# LEDLayout.net
KiCad netlist of a schematic drawn in EAGLE
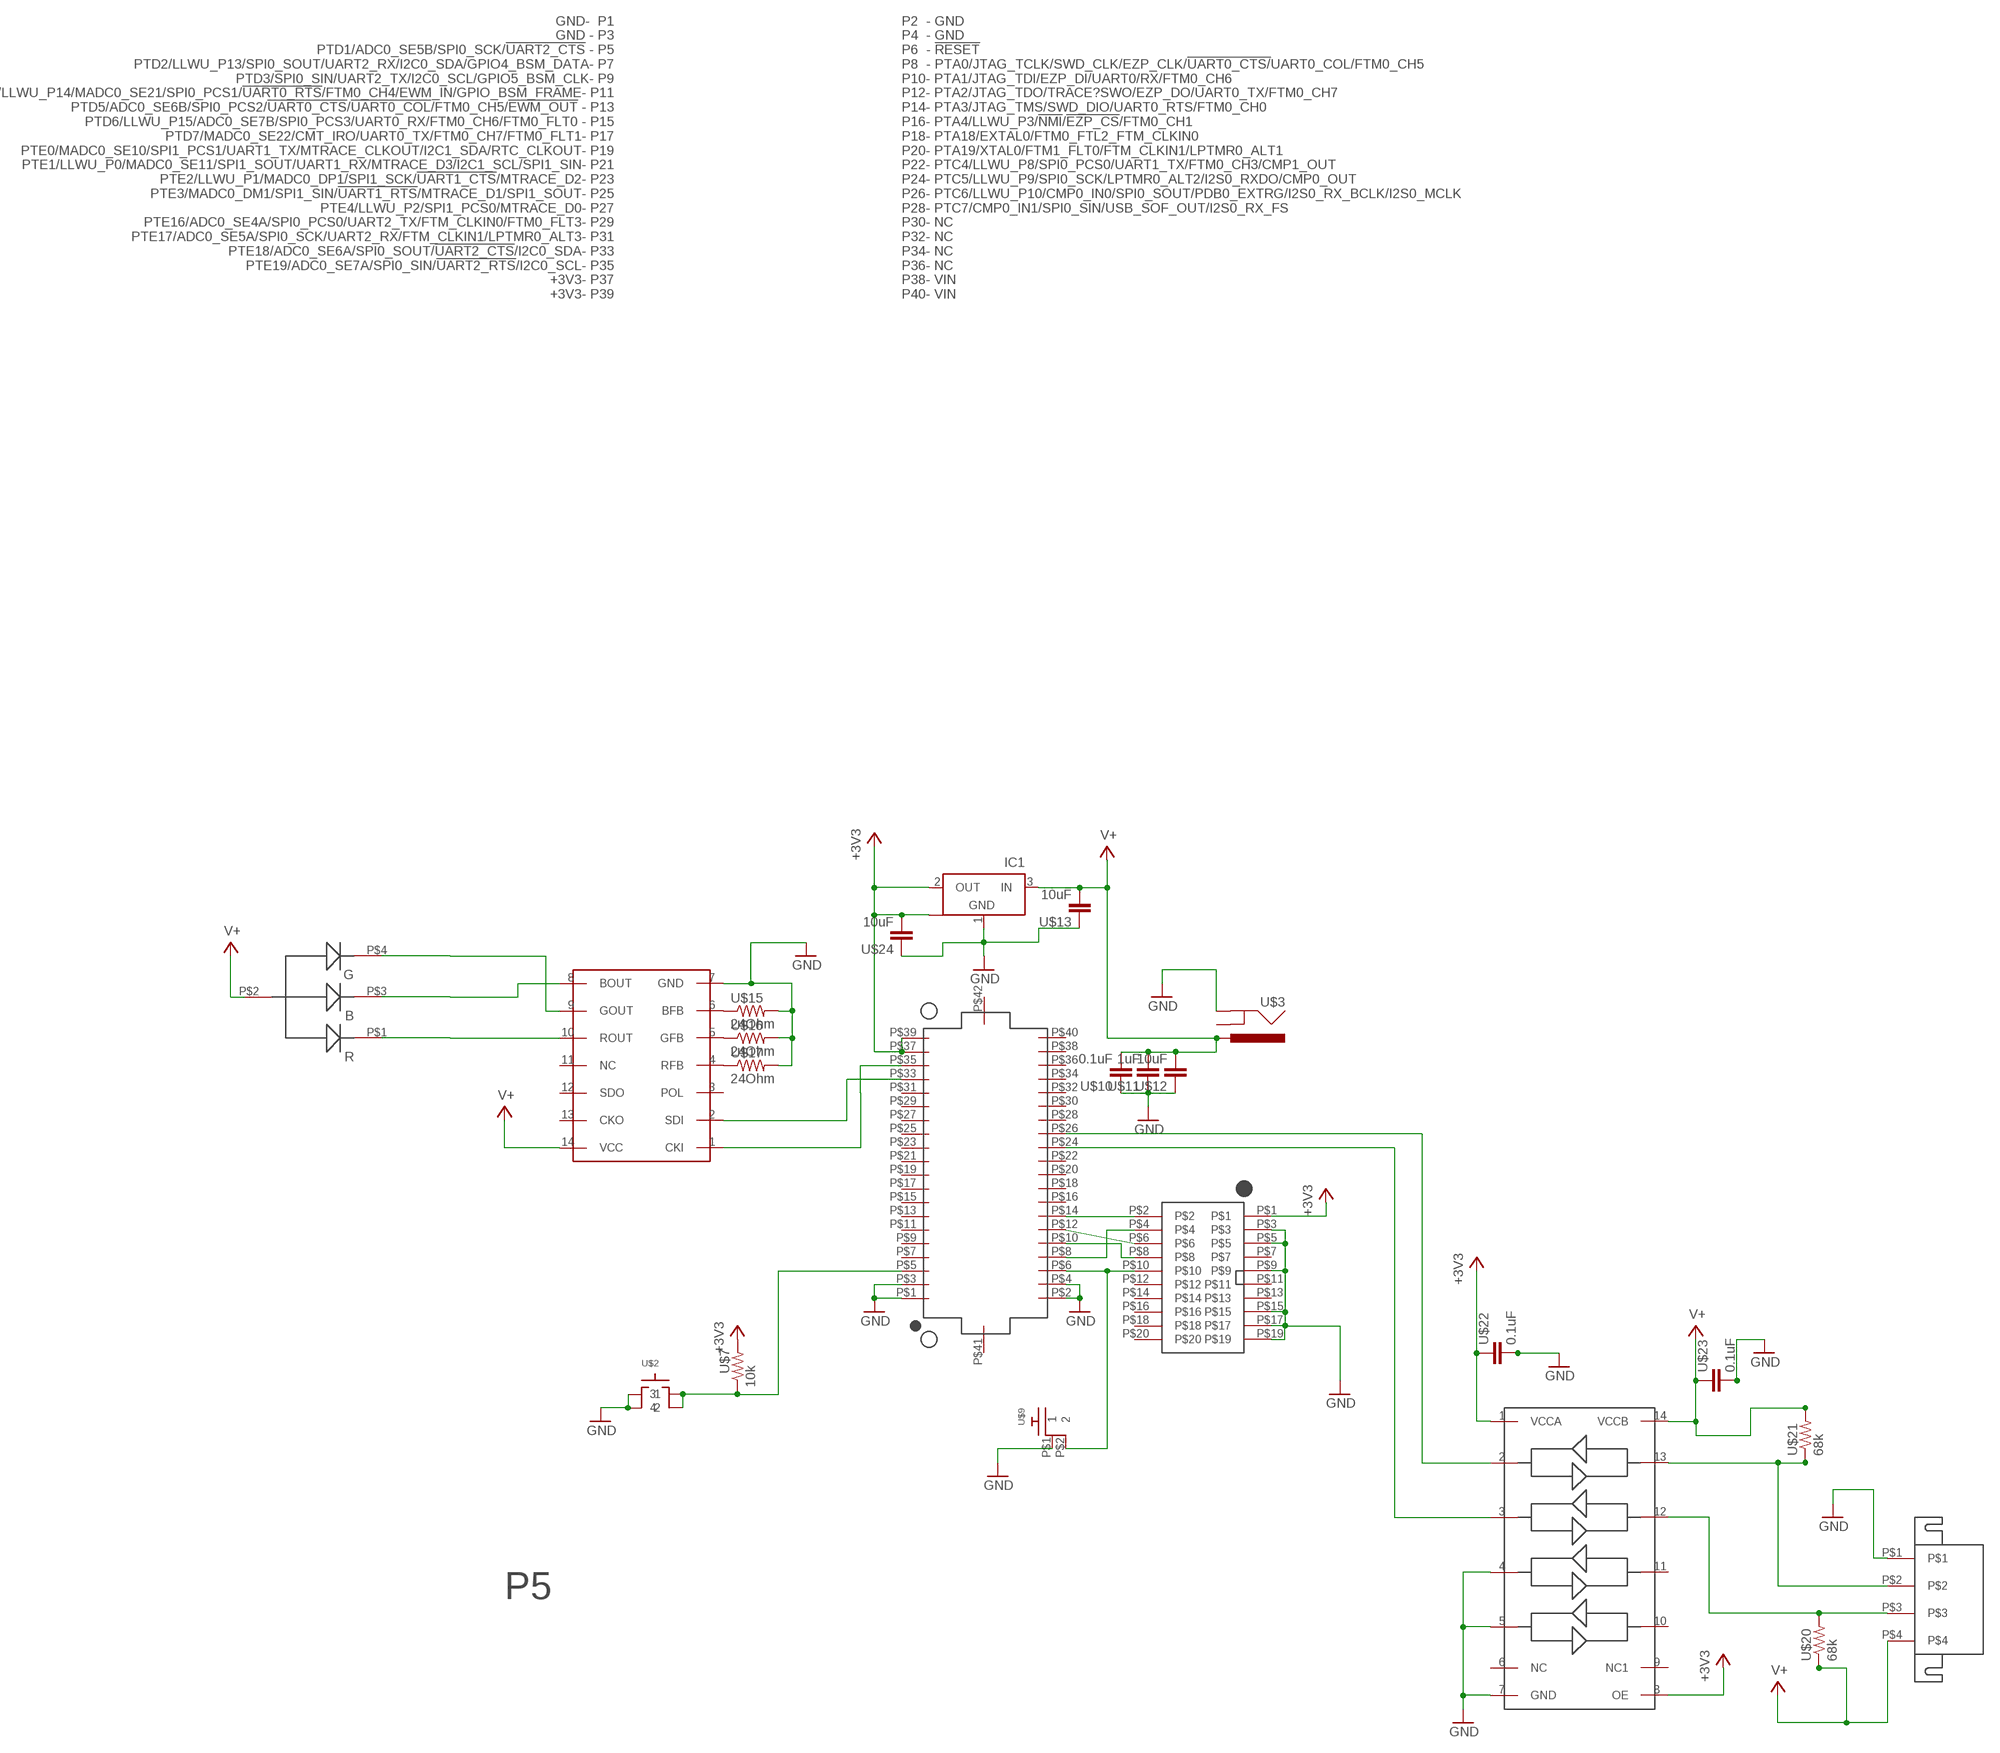
[diagram p0: schematic, sheet 1]

(export (version "E")
  (design (tool "Eeschema 10.0.6"))
  (components
    (comp (ref "IC1")
      (value "NCP1117ST33T3G_1")
      (footprint "eagle-import:SOT223")
      (fields (field (name "MFGN") "OnSemi") (field (name "MFGP") "NCP1117ST33T3G"))
      (libsource (lib "eagle-import") (part "NCP1117ST33T3G_1"))
    )
    (comp (ref "U$1")
      (value "MATE-N-LOK_643230-1")
      (footprint "eagle-import:MATE-N-LOK_643230-1")
      (fields (field (name "MFGN") "TE Connectivity") (field (name "MFGP") "643230-1"))
      (libsource (lib "eagle-import") (part "MATE-N-LOK_643230-1"))
    )
    (comp (ref "U$2")
      (value "SWITCH-TACTILE")
      (footprint "eagle-import:ESWITCH-TL3301PF")
      (libsource (lib "eagle-import") (part "SWITCH-TACTILE"))
    )
    (comp (ref "U$3")
      (value "BARREL_CUI_PJ-002A")
      (footprint "eagle-import:BARREL_CUI_PJ-002A")
      (libsource (lib "eagle-import") (part "BARREL_CUI_PJ-002A"))
    )
    (comp (ref "U$4")
      (value "DF12_F")
      (footprint "eagle-import:DF12_F")
      (fields (field (name "MFGN") "Hirose") (field (name "MFGP") "DF12(3.0)-40DP-0.5V(86)"))
      (libsource (lib "eagle-import") (part "DF12_F"))
    )
    (comp (ref "U$5")
      (value "RGLBED")
      (footprint "eagle-import:RGBLED")
      (libsource (lib "eagle-import") (part "RGLBED"))
    )
    (comp (ref "U$6")
      (value "TXB0104")
      (footprint "eagle-import:PW_R-PDSO-G14")
      (fields (field (name "MFGN") "Texas Instruments"))
      (libsource (lib "eagle-import") (part "TXB0104"))
    )
    (comp (ref "U$7")
      (value "10k")
      (footprint "eagle-import:RF-C0805")
      (libsource (lib "eagle-import") (part "RF-R0805"))
    )
    (comp (ref "U$8")
      (value "WS2801")
      (footprint "eagle-import:SO14")
      (libsource (lib "eagle-import") (part "WS2801"))
    )
    (comp (ref "U$9")
      (value "RA_BUTTON")
      (footprint "eagle-import:RA_BUTTON")
      (libsource (lib "eagle-import") (part "RA_BUTTON"))
    )
    (comp (ref "U$10")
      (value "0.1uF")
      (footprint "eagle-import:C0805")
      (libsource (lib "eagle-import") (part "RF-C0805"))
    )
    (comp (ref "U$11")
      (value "1uF")
      (footprint "eagle-import:C0805")
      (libsource (lib "eagle-import") (part "RF-C0805"))
    )
    (comp (ref "U$12")
      (value "10uF")
      (footprint "eagle-import:C0805")
      (libsource (lib "eagle-import") (part "RF-C0805"))
    )
    (comp (ref "U$13")
      (value "10uF")
      (footprint "eagle-import:C0805")
      (libsource (lib "eagle-import") (part "RF-C0805"))
    )
    (comp (ref "U$15")
      (value "24Ohm")
      (footprint "eagle-import:RF-C0805")
      (libsource (lib "eagle-import") (part "RF-R0805"))
    )
    (comp (ref "U$16")
      (value "24Ohm")
      (footprint "eagle-import:RF-C0805")
      (libsource (lib "eagle-import") (part "RF-R0805"))
    )
    (comp (ref "U$17")
      (value "24Ohm")
      (footprint "eagle-import:RF-C0805")
      (libsource (lib "eagle-import") (part "RF-R0805"))
    )
    (comp (ref "U$19")
      (value "2X10JTAG")
      (footprint "eagle-import:2X10JTAG")
      (libsource (lib "eagle-import") (part "2X10JTAG"))
    )
    (comp (ref "U$20")
      (value "68k")
      (footprint "eagle-import:RF-C0805")
      (libsource (lib "eagle-import") (part "RF-R0805"))
    )
    (comp (ref "U$21")
      (value "68k")
      (footprint "eagle-import:RF-C0805")
      (libsource (lib "eagle-import") (part "RF-R0805"))
    )
    (comp (ref "U$22")
      (value "0.1uF")
      (footprint "eagle-import:C0805")
      (libsource (lib "eagle-import") (part "RF-C0805"))
    )
    (comp (ref "U$23")
      (value "0.1uF")
      (footprint "eagle-import:C0805")
      (libsource (lib "eagle-import") (part "RF-C0805"))
    )
    (comp (ref "U$24")
      (value "10uF")
      (footprint "eagle-import:C0805")
      (libsource (lib "eagle-import") (part "RF-C0805"))
    )
  )
  (nets
    (net (code "1") (name "+3V3") (class "Default")
      (node (ref "IC1") (pin "2") (pinfunction "OUT_2") (pintype "power_in"))
      (node (ref "IC1") (pin "4") (pinfunction "OUT1_4") (pintype "power_in"))
      (node (ref "U$19") (pin "P$1") (pinfunction "P$1_P$1") (pintype "bidirectional"))
      (node (ref "U$22") (pin "1") (pinfunction "1_1") (pintype "passive"))
      (node (ref "U$24") (pin "2") (pinfunction "2_2") (pintype "passive"))
      (node (ref "U$4") (pin "P$37") (pinfunction "+3V3_P$37") (pintype "bidirectional"))
      (node (ref "U$4") (pin "P$39") (pinfunction "+3V3_P$39") (pintype "bidirectional"))
      (node (ref "U$6") (pin "1") (pinfunction "VCCA_1") (pintype "bidirectional"))
      (node (ref "U$6") (pin "8") (pinfunction "OE_8") (pintype "bidirectional"))
      (node (ref "U$7") (pin "2") (pinfunction "2_2") (pintype "passive"))
    )
    (net (code "2") (name "GND") (class "Default")
      (node (ref "IC1") (pin "1") (pinfunction "GND_1") (pintype "power_in"))
      (node (ref "U$1") (pin "P$1") (pinfunction "P$1_P$1") (pintype "bidirectional"))
      (node (ref "U$10") (pin "1") (pinfunction "1_1") (pintype "passive"))
      (node (ref "U$11") (pin "1") (pinfunction "1_1") (pintype "passive"))
      (node (ref "U$12") (pin "1") (pinfunction "1_1") (pintype "passive"))
      (node (ref "U$13") (pin "1") (pinfunction "1_1") (pintype "passive"))
      (node (ref "U$15") (pin "2") (pinfunction "2_2") (pintype "passive"))
      (node (ref "U$16") (pin "2") (pinfunction "2_2") (pintype "passive"))
      (node (ref "U$17") (pin "2") (pinfunction "2_2") (pintype "passive"))
      (node (ref "U$19") (pin "P$15") (pinfunction "P$15_P$15") (pintype "bidirectional"))
      (node (ref "U$19") (pin "P$17") (pinfunction "P$17_P$17") (pintype "bidirectional"))
      (node (ref "U$19") (pin "P$19") (pinfunction "P$19_P$19") (pintype "bidirectional"))
      (node (ref "U$19") (pin "P$3") (pinfunction "P$3_P$3") (pintype "bidirectional"))
      (node (ref "U$19") (pin "P$5") (pinfunction "P$5_P$5") (pintype "bidirectional"))
      (node (ref "U$19") (pin "P$9") (pinfunction "P$9_P$9") (pintype "bidirectional"))
      (node (ref "U$2") (pin "1") (pinfunction "1_1") (pintype "input"))
      (node (ref "U$2") (pin "2") (pinfunction "2_2") (pintype "input"))
      (node (ref "U$22") (pin "2") (pinfunction "2_2") (pintype "passive"))
      (node (ref "U$23") (pin "2") (pinfunction "2_2") (pintype "passive"))
      (node (ref "U$24") (pin "1") (pinfunction "1_1") (pintype "passive"))
      (node (ref "U$3") (pin "P$2") (pinfunction "GND_P$2") (pintype "bidirectional"))
      (node (ref "U$4") (pin "P$1") (pinfunction "GND_P$1") (pintype "bidirectional"))
      (node (ref "U$4") (pin "P$2") (pinfunction "GND_P$2") (pintype "bidirectional"))
      (node (ref "U$4") (pin "P$3") (pinfunction "GND_P$3") (pintype "bidirectional"))
      (node (ref "U$4") (pin "P$4") (pinfunction "GND_P$4") (pintype "bidirectional"))
      (node (ref "U$6") (pin "4") (pinfunction "P$4_4") (pintype "bidirectional"))
      (node (ref "U$6") (pin "5") (pinfunction "P$5_5") (pintype "bidirectional"))
      (node (ref "U$6") (pin "7") (pinfunction "GND_7") (pintype "bidirectional"))
      (node (ref "U$8") (pin "7") (pinfunction "GND_7") (pintype "bidirectional"))
      (node (ref "U$9") (pin "P$1") (pinfunction "1_P$1") (pintype "input"))
    )
    (net (code "3") (name "Net-(U$4-PTA0{slash}JTAG_TCLK{slash}SWD_CLK{slash}EZP_CLK{slash}~{UART0_CTS{slash}}UART0_COL{slash}FTM0_CH5)") (class "Default")
      (node (ref "U$19") (pin "P$4") (pinfunction "P$4_P$4") (pintype "bidirectional"))
      (node (ref "U$4") (pin "P$8") (pinfunction "PTA0/JTAG_TCLK/SWD_CLK/EZP_CLK/~{UART0_CTS/}UART0_COL/FTM0_CH5_P$8") (pintype "bidirectional"))
    )
    (net (code "4") (name "Net-(U$4-PTA1{slash}JTAG_TDI{slash}EZP_DI{slash}UART0{slash}RX{slash}FTM0_CH6)") (class "Default")
      (node (ref "U$19") (pin "P$8") (pinfunction "P$8_P$8") (pintype "bidirectional"))
      (node (ref "U$4") (pin "P$10") (pinfunction "PTA1/JTAG_TDI/EZP_DI/UART0/RX/FTM0_CH6_P$10") (pintype "bidirectional"))
    )
    (net (code "5") (name "Net-(U$4-PTA2{slash}JTAG_TDO{slash}TRACE?SWO{slash}EZP_DO{slash}UART0_TX{slash}FTM0_CH7)") (class "Default")
      (node (ref "U$19") (pin "P$6") (pinfunction "P$6_P$6") (pintype "bidirectional"))
      (node (ref "U$4") (pin "P$12") (pinfunction "PTA2/JTAG_TDO/TRACE?SWO/EZP_DO/UART0_TX/FTM0_CH7_P$12") (pintype "bidirectional"))
    )
    (net (code "6") (name "Net-(U$4-PTA3{slash}JTAG_TMS{slash}SWD_DIO{slash}UART0_RTS{slash}FTM0_CH0)") (class "Default")
      (node (ref "U$19") (pin "P$2") (pinfunction "P$2_P$2") (pintype "bidirectional"))
      (node (ref "U$4") (pin "P$14") (pinfunction "PTA3/JTAG_TMS/SWD_DIO/UART0_RTS/FTM0_CH0_P$14") (pintype "bidirectional"))
    )
    (net (code "7") (name "Net-(U$4-PTC5{slash}LLWU_P8{slash}SPI0_PCS0{slash}UART1_TX{slash}FTM0_CH3{slash}CMP1_OUT)") (class "Default")
      (node (ref "U$4") (pin "P$24") (pinfunction "PTC5/LLWU_P8/SPI0_PCS0/UART1_TX/FTM0_CH3/CMP1_OUT_P$24") (pintype "bidirectional"))
      (node (ref "U$6") (pin "3") (pinfunction "P$3_3") (pintype "bidirectional"))
    )
    (net (code "8") (name "Net-(U$4-PTC6{slash}LLWU_P10{slash}CMP0_IN0{slash}SPI0_SOUT{slash}PDB0_EXTRG{slash}I2S0_RX_BCLK{slash}I2S0_MCLK)") (class "Default")
      (node (ref "U$4") (pin "P$26") (pinfunction "PTC6/LLWU_P10/CMP0_IN0/SPI0_SOUT/PDB0_EXTRG/I2S0_RX_BCLK/I2S0_MCLK_P$26") (pintype "bidirectional"))
      (node (ref "U$6") (pin "2") (pinfunction "P$2_2") (pintype "bidirectional"))
    )
    (net (code "9") (name "Net-(U$4-PTD1{slash}ADC0_SE5B{slash}SPI0_SCK{slash}~{UART2_CTS})") (class "Default")
      (node (ref "U$2") (pin "3") (pinfunction "3_3") (pintype "input"))
      (node (ref "U$2") (pin "4") (pinfunction "4_4") (pintype "input"))
      (node (ref "U$4") (pin "P$5") (pinfunction "PTD1/ADC0_SE5B/SPI0_SCK/~{UART2_CTS}_P$5") (pintype "bidirectional"))
      (node (ref "U$7") (pin "1") (pinfunction "1_1") (pintype "passive"))
    )
    (net (code "10") (name "Net-(U$4-PTE18{slash}ADC0_SE6A{slash}SPI0_SOUT{slash}~{UART2_CTS}{slash}I2C0_SDA)") (class "Default")
      (node (ref "U$4") (pin "P$33") (pinfunction "PTE18/ADC0_SE6A/SPI0_SOUT/~{UART2_CTS}/I2C0_SDA_P$33") (pintype "bidirectional"))
      (node (ref "U$8") (pin "2") (pinfunction "SDI_2") (pintype "bidirectional"))
    )
    (net (code "11") (name "Net-(U$4-PTE19{slash}ADC0_SE7A{slash}SPI0_SIN{slash}~{UART2_RTS}{slash}I2C0_SCL)") (class "Default")
      (node (ref "U$4") (pin "P$35") (pinfunction "PTE19/ADC0_SE7A/SPI0_SIN/~{UART2_RTS}/I2C0_SCL_P$35") (pintype "bidirectional"))
      (node (ref "U$8") (pin "1") (pinfunction "CKI_1") (pintype "bidirectional"))
    )
    (net (code "12") (name "Net-(U$4-~{RESET})") (class "Default")
      (node (ref "U$19") (pin "P$10") (pinfunction "P$10_P$10") (pintype "bidirectional"))
      (node (ref "U$4") (pin "P$6") (pinfunction "~{RESET}_P$6") (pintype "bidirectional"))
      (node (ref "U$9") (pin "P$2") (pinfunction "2_P$2") (pintype "input"))
    )
    (net (code "13") (name "Net-(U$5-BLUE)") (class "Default")
      (node (ref "U$5") (pin "P$3") (pinfunction "BLUE_P$3") (pintype "bidirectional"))
      (node (ref "U$8") (pin "8") (pinfunction "BOUT_8") (pintype "bidirectional"))
    )
    (net (code "14") (name "Net-(U$5-GREEN)") (class "Default")
      (node (ref "U$5") (pin "P$4") (pinfunction "GREEN_P$4") (pintype "bidirectional"))
      (node (ref "U$8") (pin "9") (pinfunction "GOUT_9") (pintype "bidirectional"))
    )
    (net (code "15") (name "Net-(U$5-RED)") (class "Default")
      (node (ref "U$5") (pin "P$1") (pinfunction "RED_P$1") (pintype "bidirectional"))
      (node (ref "U$8") (pin "10") (pinfunction "ROUT_10") (pintype "bidirectional"))
    )
    (net (code "16") (name "Net-(U$6-P$12)") (class "Default")
      (node (ref "U$1") (pin "P$3") (pinfunction "P$3_P$3") (pintype "bidirectional"))
      (node (ref "U$20") (pin "2") (pinfunction "2_2") (pintype "passive"))
      (node (ref "U$6") (pin "12") (pinfunction "P$12_12") (pintype "bidirectional"))
    )
    (net (code "17") (name "Net-(U$6-P$13)") (class "Default")
      (node (ref "U$1") (pin "P$2") (pinfunction "P$2_P$2") (pintype "bidirectional"))
      (node (ref "U$21") (pin "1") (pinfunction "1_1") (pintype "passive"))
      (node (ref "U$6") (pin "13") (pinfunction "P$13_13") (pintype "bidirectional"))
    )
    (net (code "18") (name "Net-(U$8-BFB)") (class "Default")
      (node (ref "U$15") (pin "1") (pinfunction "1_1") (pintype "passive"))
      (node (ref "U$8") (pin "6") (pinfunction "BFB_6") (pintype "bidirectional"))
    )
    (net (code "19") (name "Net-(U$8-GFB)") (class "Default")
      (node (ref "U$16") (pin "1") (pinfunction "1_1") (pintype "passive"))
      (node (ref "U$8") (pin "5") (pinfunction "GFB_5") (pintype "bidirectional"))
    )
    (net (code "20") (name "Net-(U$8-RFB)") (class "Default")
      (node (ref "U$17") (pin "1") (pinfunction "1_1") (pintype "passive"))
      (node (ref "U$8") (pin "4") (pinfunction "RFB_4") (pintype "bidirectional"))
    )
    (net (code "21") (name "V+") (class "Default")
      (node (ref "IC1") (pin "3") (pinfunction "IN_3") (pintype "input"))
      (node (ref "U$1") (pin "P$4") (pinfunction "P$4_P$4") (pintype "bidirectional"))
      (node (ref "U$10") (pin "2") (pinfunction "2_2") (pintype "passive"))
      (node (ref "U$11") (pin "2") (pinfunction "2_2") (pintype "passive"))
      (node (ref "U$12") (pin "2") (pinfunction "2_2") (pintype "passive"))
      (node (ref "U$13") (pin "2") (pinfunction "2_2") (pintype "passive"))
      (node (ref "U$20") (pin "1") (pinfunction "1_1") (pintype "passive"))
      (node (ref "U$21") (pin "2") (pinfunction "2_2") (pintype "passive"))
      (node (ref "U$23") (pin "1") (pinfunction "1_1") (pintype "passive"))
      (node (ref "U$3") (pin "P$1") (pinfunction "PWR_P$1") (pintype "bidirectional"))
      (node (ref "U$5") (pin "P$2") (pinfunction "ANODE_P$2") (pintype "bidirectional"))
      (node (ref "U$6") (pin "14") (pinfunction "VCCB_14") (pintype "bidirectional"))
      (node (ref "U$8") (pin "14") (pinfunction "VCC_14") (pintype "bidirectional"))
    )
    (net (code "22") (name "unconnected-(U$3-GNDBREAK-PadP$3)") (class "Default")
      (node (ref "U$3") (pin "P$3") (pinfunction "GNDBREAK_P$3") (pintype "bidirectional"))
    )
    (net (code "23") (name "unconnected-(U$4-NC-PadP$30)") (class "Default")
      (node (ref "U$4") (pin "P$30") (pinfunction "NC_P$30") (pintype "bidirectional"))
    )
    (net (code "24") (name "unconnected-(U$4-NC-PadP$32)") (class "Default")
      (node (ref "U$4") (pin "P$32") (pinfunction "NC_P$32") (pintype "bidirectional"))
    )
    (net (code "25") (name "unconnected-(U$4-NC-PadP$34)") (class "Default")
      (node (ref "U$4") (pin "P$34") (pinfunction "NC_P$34") (pintype "bidirectional"))
    )
    (net (code "26") (name "unconnected-(U$4-NC-PadP$36)") (class "Default")
      (node (ref "U$4") (pin "P$36") (pinfunction "NC_P$36") (pintype "bidirectional"))
    )
    (net (code "27") (name "unconnected-(U$4-PTA4{slash}LLWU_P3{slash}~{NMI}{slash}~{EZP_CS}{slash}FTM0_CH1-PadP$16)") (class "Default")
      (node (ref "U$4") (pin "P$16") (pinfunction "PTA4/LLWU_P3/~{NMI}/~{EZP_CS}/FTM0_CH1_P$16") (pintype "bidirectional"))
    )
    (net (code "28") (name "unconnected-(U$4-PTA18{slash}EXTAL0{slash}FTM0_FTL2_FTM_CLKIN0-PadP$18)") (class "Default")
      (node (ref "U$4") (pin "P$18") (pinfunction "PTA18/EXTAL0/FTM0_FTL2_FTM_CLKIN0_P$18") (pintype "bidirectional"))
    )
    (net (code "29") (name "unconnected-(U$4-PTA19{slash}XTAL0{slash}FTM1_FLT0{slash}FTM_CLKIN1{slash}LPTMR0_ALT1-PadP$20)") (class "Default")
      (node (ref "U$4") (pin "P$20") (pinfunction "PTA19/XTAL0/FTM1_FLT0/FTM_CLKIN1/LPTMR0_ALT1_P$20") (pintype "bidirectional"))
    )
    (net (code "30") (name "unconnected-(U$4-PTC4{slash}LLWU_P8{slash}SPI0_PCS0{slash}UART1_TX{slash}FTM0_CH3{slash}CMP1_OUT-PadP$22)") (class "Default")
      (node (ref "U$4") (pin "P$22") (pinfunction "PTC4/LLWU_P8/SPI0_PCS0/UART1_TX/FTM0_CH3/CMP1_OUT_P$22") (pintype "bidirectional"))
    )
    (net (code "31") (name "unconnected-(U$4-PTC7{slash}CMP0_IN1{slash}SPI0_SIN{slash}USB_SOF_OUT{slash}I2S0_RX_FS-PadP$28)") (class "Default")
      (node (ref "U$4") (pin "P$28") (pinfunction "PTC7/CMP0_IN1/SPI0_SIN/USB_SOF_OUT/I2S0_RX_FS_P$28") (pintype "bidirectional"))
    )
    (net (code "32") (name "unconnected-(U$4-PTD2{slash}LLWU_P13{slash}SPI0_SOUT{slash}UART2_RX{slash}I2C0_SDA{slash}GPIO4_BSM_DATA-PadP$7)") (class "Default")
      (node (ref "U$4") (pin "P$7") (pinfunction "PTD2/LLWU_P13/SPI0_SOUT/UART2_RX/I2C0_SDA/GPIO4_BSM_DATA_P$7") (pintype "bidirectional"))
    )
    (net (code "33") (name "unconnected-(U$4-PTD3{slash}SPI0_SIN{slash}UART2_TX{slash}I2C0_SCL{slash}GPIO5_BSM_CLK-PadP$9)") (class "Default")
      (node (ref "U$4") (pin "P$9") (pinfunction "PTD3/SPI0_SIN/UART2_TX/I2C0_SCL/GPIO5_BSM_CLK_P$9") (pintype "bidirectional"))
    )
    (net (code "34") (name "unconnected-(U$4-PTD4{slash}LLWU_P14{slash}MADC0_SE21{slash}SPI0_PCS1{slash}~{UART0_RTS}{slash}FTM0_CH4{slash}EWM_IN{slash}GPIO_BSM_FRAME-PadP$11)") (class "Default")
      (node (ref "U$4") (pin "P$11") (pinfunction "PTD4/LLWU_P14/MADC0_SE21/SPI0_PCS1/~{UART0_RTS}/FTM0_CH4/EWM_IN/GPIO_BSM_FRAME_P$11") (pintype "bidirectional"))
    )
    (net (code "35") (name "unconnected-(U$4-PTD5{slash}ADC0_SE6B{slash}SPI0_PCS2{slash}~{UART0_CTS}{slash}~{UART0_COL}{slash}FTM0_CH5{slash}~{EWM_OUT}-PadP$13)") (class "Default")
      (node (ref "U$4") (pin "P$13") (pinfunction "PTD5/ADC0_SE6B/SPI0_PCS2/~{UART0_CTS}/~{UART0_COL}/FTM0_CH5/~{EWM_OUT}_P$13") (pintype "bidirectional"))
    )
    (net (code "36") (name "unconnected-(U$4-PTD6{slash}LLWU_P15{slash}ADC0_SE7B{slash}SPI0_PCS3{slash}UART0_RX{slash}FTM0_CH6{slash}FTM0_FLT0-PadP$15)") (class "Default")
      (node (ref "U$4") (pin "P$15") (pinfunction "PTD6/LLWU_P15/ADC0_SE7B/SPI0_PCS3/UART0_RX/FTM0_CH6/FTM0_FLT0_P$15") (pintype "bidirectional"))
    )
    (net (code "37") (name "unconnected-(U$4-PTD7{slash}MADC0_SE22{slash}CMT_IRO{slash}UART0_TX{slash}FTM0_CH7{slash}FTM0_FLT1-PadP$17)") (class "Default")
      (node (ref "U$4") (pin "P$17") (pinfunction "PTD7/MADC0_SE22/CMT_IRO/UART0_TX/FTM0_CH7/FTM0_FLT1_P$17") (pintype "bidirectional"))
    )
    (net (code "38") (name "unconnected-(U$4-PTE0{slash}MADC0_SE10{slash}SPI1_PCS1{slash}UART1_TX{slash}MTRACE_CLKOUT{slash}I2C1_SDA{slash}RTC_CLKOUT-PadP$19)") (class "Default")
      (node (ref "U$4") (pin "P$19") (pinfunction "PTE0/MADC0_SE10/SPI1_PCS1/UART1_TX/MTRACE_CLKOUT/I2C1_SDA/RTC_CLKOUT_P$19") (pintype "bidirectional"))
    )
    (net (code "39") (name "unconnected-(U$4-PTE1{slash}LLWU_P0{slash}MADC0_SE11{slash}SPI1_SOUT{slash}UART1_RX{slash}MTRACE_D3{slash}I2C1_SCL{slash}SPI1_SIN-PadP$21)") (class "Default")
      (node (ref "U$4") (pin "P$21") (pinfunction "PTE1/LLWU_P0/MADC0_SE11/SPI1_SOUT/UART1_RX/MTRACE_D3/I2C1_SCL/SPI1_SIN_P$21") (pintype "bidirectional"))
    )
    (net (code "40") (name "unconnected-(U$4-PTE2{slash}LLWU_P1{slash}MADC0_DP1{slash}SPI1_SCK{slash}~{UART1_CTS}{slash}MTRACE_D2-PadP$23)") (class "Default")
      (node (ref "U$4") (pin "P$23") (pinfunction "PTE2/LLWU_P1/MADC0_DP1/SPI1_SCK/~{UART1_CTS}/MTRACE_D2_P$23") (pintype "bidirectional"))
    )
    (net (code "41") (name "unconnected-(U$4-PTE3{slash}MADC0_DM1{slash}SPI1_SIN{slash}~{UART1_RTS}{slash}MTRACE_D1{slash}SPI1_SOUT-PadP$25)") (class "Default")
      (node (ref "U$4") (pin "P$25") (pinfunction "PTE3/MADC0_DM1/SPI1_SIN/~{UART1_RTS}/MTRACE_D1/SPI1_SOUT_P$25") (pintype "bidirectional"))
    )
    (net (code "42") (name "unconnected-(U$4-PTE4{slash}LLWU_P2{slash}SPI1_PCS0{slash}MTRACE_D0-PadP$27)") (class "Default")
      (node (ref "U$4") (pin "P$27") (pinfunction "PTE4/LLWU_P2/SPI1_PCS0/MTRACE_D0_P$27") (pintype "bidirectional"))
    )
    (net (code "43") (name "unconnected-(U$4-PTE16{slash}ADC0_SE4A{slash}SPI0_PCS0{slash}UART2_TX{slash}FTM_CLKIN0{slash}FTM0_FLT3-PadP$29)") (class "Default")
      (node (ref "U$4") (pin "P$29") (pinfunction "PTE16/ADC0_SE4A/SPI0_PCS0/UART2_TX/FTM_CLKIN0/FTM0_FLT3_P$29") (pintype "bidirectional"))
    )
    (net (code "44") (name "unconnected-(U$4-PTE17{slash}ADC0_SE5A{slash}SPI0_SCK{slash}UART2_RX{slash}FTM_CLKIN1{slash}LPTMR0_ALT3-PadP$31)") (class "Default")
      (node (ref "U$4") (pin "P$31") (pinfunction "PTE17/ADC0_SE5A/SPI0_SCK/UART2_RX/FTM_CLKIN1/LPTMR0_ALT3_P$31") (pintype "bidirectional"))
    )
    (net (code "45") (name "unconnected-(U$4-PadP$41)") (class "Default")
      (node (ref "U$4") (pin "P$41") (pinfunction "P$41_P$41") (pintype "bidirectional"))
    )
    (net (code "46") (name "unconnected-(U$4-PadP$42)") (class "Default")
      (node (ref "U$4") (pin "P$42") (pinfunction "P$42_P$42") (pintype "bidirectional"))
    )
    (net (code "47") (name "unconnected-(U$4-VIN-PadP$38)") (class "Default")
      (node (ref "U$4") (pin "P$38") (pinfunction "VIN_P$38") (pintype "bidirectional"))
    )
    (net (code "48") (name "unconnected-(U$4-VIN-PadP$40)") (class "Default")
      (node (ref "U$4") (pin "P$40") (pinfunction "VIN_P$40") (pintype "bidirectional"))
    )
    (net (code "49") (name "unconnected-(U$6-NC-Pad6)") (class "Default")
      (node (ref "U$6") (pin "6") (pinfunction "NC_6") (pintype "bidirectional"))
    )
    (net (code "50") (name "unconnected-(U$6-NC1-Pad9)") (class "Default")
      (node (ref "U$6") (pin "9") (pinfunction "NC1_9") (pintype "bidirectional"))
    )
    (net (code "51") (name "unconnected-(U$6-P$10-Pad10)") (class "Default")
      (node (ref "U$6") (pin "10") (pinfunction "P$10_10") (pintype "bidirectional"))
    )
    (net (code "52") (name "unconnected-(U$6-P$11-Pad11)") (class "Default")
      (node (ref "U$6") (pin "11") (pinfunction "P$11_11") (pintype "bidirectional"))
    )
    (net (code "53") (name "unconnected-(U$8-CKO-Pad13)") (class "Default")
      (node (ref "U$8") (pin "13") (pinfunction "CKO_13") (pintype "bidirectional"))
    )
    (net (code "54") (name "unconnected-(U$8-NC-Pad11)") (class "Default")
      (node (ref "U$8") (pin "11") (pinfunction "NC_11") (pintype "bidirectional"))
    )
    (net (code "55") (name "unconnected-(U$8-POL-Pad3)") (class "Default")
      (node (ref "U$8") (pin "3") (pinfunction "POL_3") (pintype "bidirectional"))
    )
    (net (code "56") (name "unconnected-(U$8-SDO-Pad12)") (class "Default")
      (node (ref "U$8") (pin "12") (pinfunction "SDO_12") (pintype "bidirectional"))
    )
    (net (code "57") (name "unconnected-(U$19-PadP$7)") (class "Default")
      (node (ref "U$19") (pin "P$7") (pinfunction "P$7_P$7") (pintype "bidirectional"))
    )
    (net (code "58") (name "unconnected-(U$19-PadP$11)") (class "Default")
      (node (ref "U$19") (pin "P$11") (pinfunction "P$11_P$11") (pintype "bidirectional"))
    )
    (net (code "59") (name "unconnected-(U$19-PadP$12)") (class "Default")
      (node (ref "U$19") (pin "P$12") (pinfunction "P$12_P$12") (pintype "bidirectional"))
    )
    (net (code "60") (name "unconnected-(U$19-PadP$13)") (class "Default")
      (node (ref "U$19") (pin "P$13") (pinfunction "P$13_P$13") (pintype "bidirectional"))
    )
    (net (code "61") (name "unconnected-(U$19-PadP$14)") (class "Default")
      (node (ref "U$19") (pin "P$14") (pinfunction "P$14_P$14") (pintype "bidirectional"))
    )
    (net (code "62") (name "unconnected-(U$19-PadP$16)") (class "Default")
      (node (ref "U$19") (pin "P$16") (pinfunction "P$16_P$16") (pintype "bidirectional"))
    )
    (net (code "63") (name "unconnected-(U$19-PadP$18)") (class "Default")
      (node (ref "U$19") (pin "P$18") (pinfunction "P$18_P$18") (pintype "bidirectional"))
    )
    (net (code "64") (name "unconnected-(U$19-PadP$20)") (class "Default")
      (node (ref "U$19") (pin "P$20") (pinfunction "P$20_P$20") (pintype "bidirectional"))
    )
  )
)
